# W010A.net
KiCad netlist of a schematic drawn in EAGLE
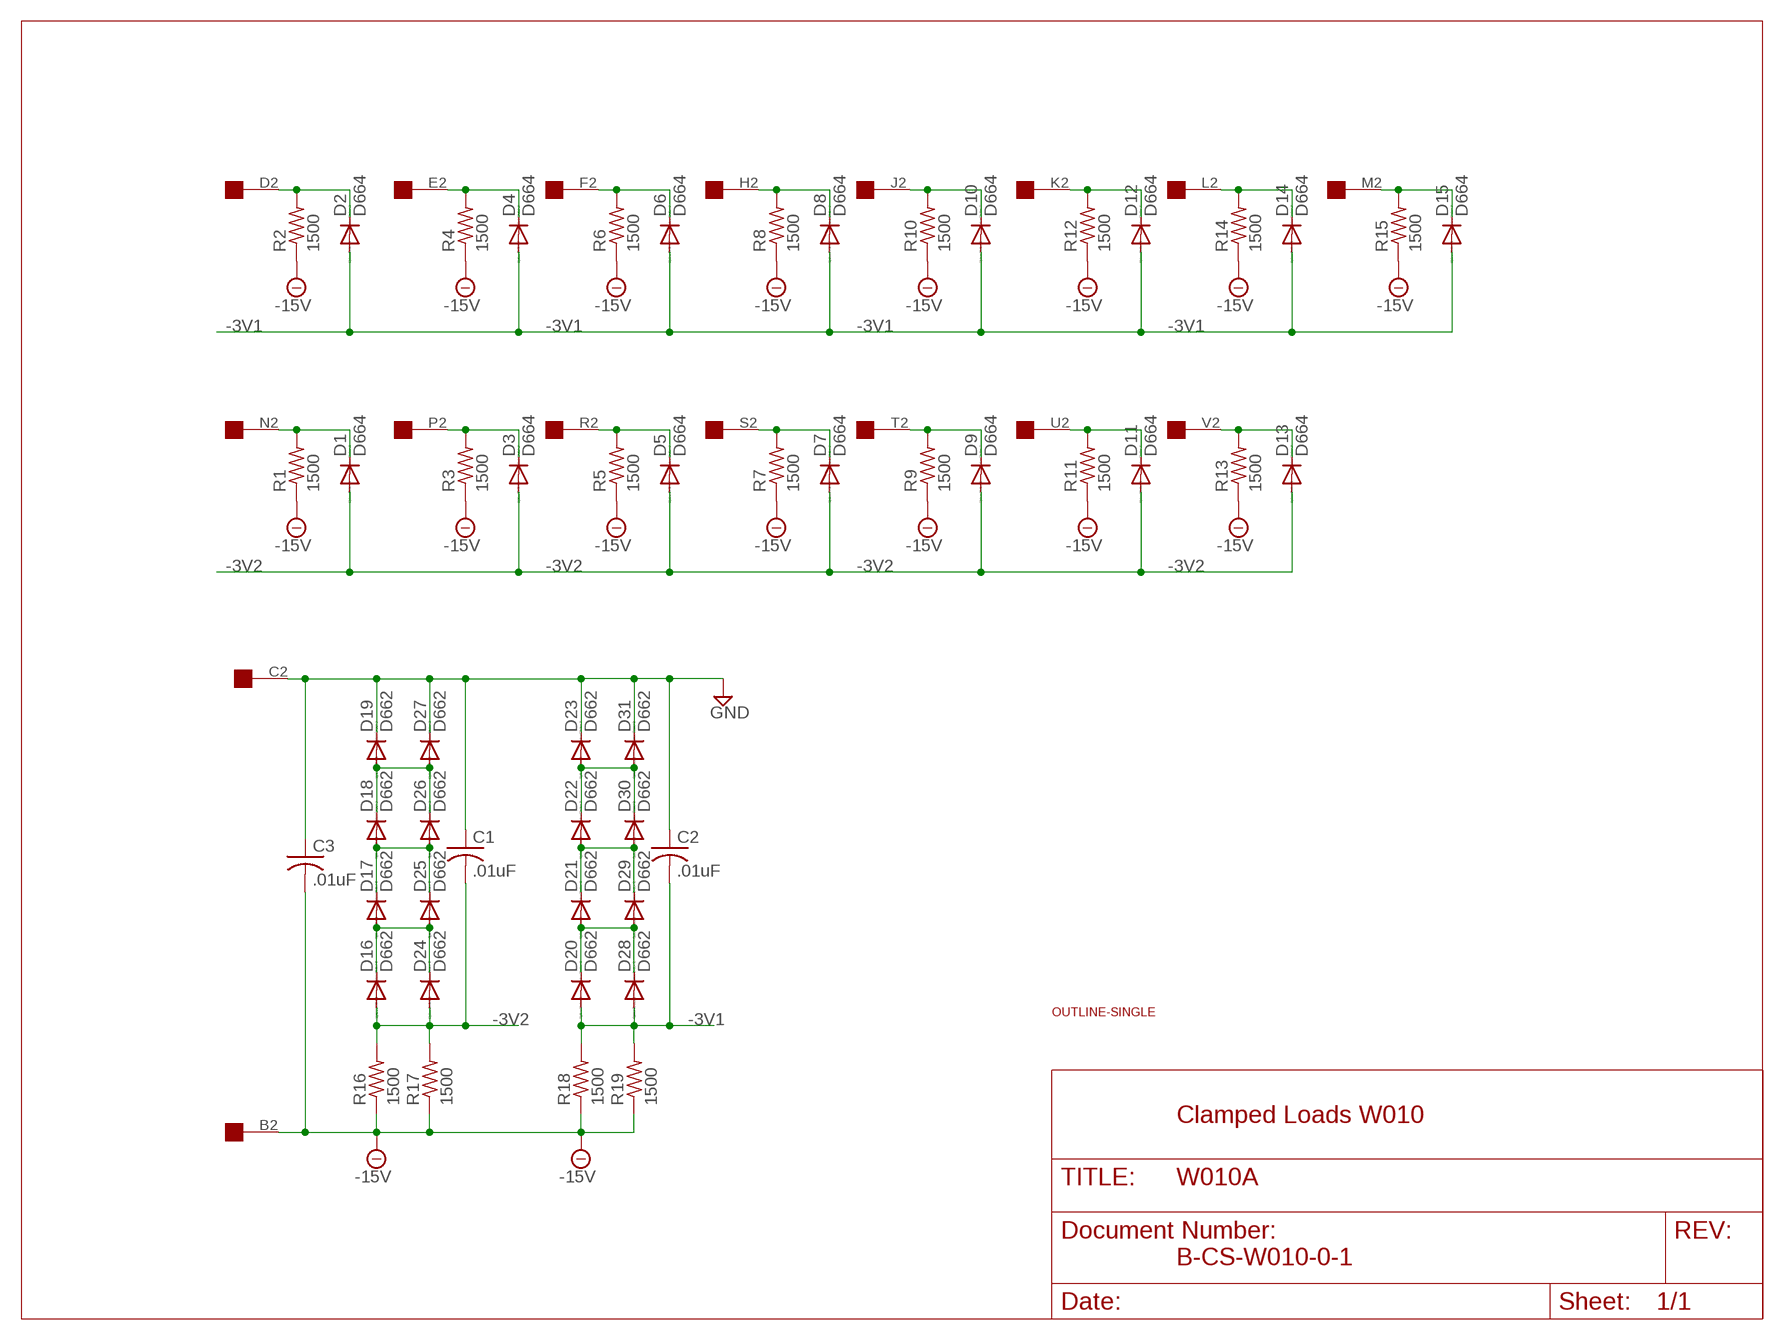
[diagram p0: schematic, sheet 1]

(export (version "E")
  (design (tool "Eeschema 10.0.6"))
  (components
    (comp (ref "C1")
      (value ".01uF")
      (footprint "eagle-import:C063-025X075")
      (libsource (lib "eagle-import") (part "C-US"))
    )
    (comp (ref "C2")
      (value ".01uF")
      (footprint "eagle-import:C063-025X075")
      (libsource (lib "eagle-import") (part "C-US"))
    )
    (comp (ref "C3")
      (value ".01uF")
      (footprint "eagle-import:C063-025X075")
      (libsource (lib "eagle-import") (part "C-US"))
    )
    (comp (ref "D1")
      (value "D664")
      (footprint "eagle-import:DO35-10")
      (libsource (lib "eagle-import") (part "DIODE-DO35-10"))
    )
    (comp (ref "D2")
      (value "D664")
      (footprint "eagle-import:DO35-10")
      (libsource (lib "eagle-import") (part "DIODE-DO35-10"))
    )
    (comp (ref "D3")
      (value "D664")
      (footprint "eagle-import:DO35-10")
      (libsource (lib "eagle-import") (part "DIODE-DO35-10"))
    )
    (comp (ref "D4")
      (value "D664")
      (footprint "eagle-import:DO35-10")
      (libsource (lib "eagle-import") (part "DIODE-DO35-10"))
    )
    (comp (ref "D5")
      (value "D664")
      (footprint "eagle-import:DO35-10")
      (libsource (lib "eagle-import") (part "DIODE-DO35-10"))
    )
    (comp (ref "D6")
      (value "D664")
      (footprint "eagle-import:DO35-10")
      (libsource (lib "eagle-import") (part "DIODE-DO35-10"))
    )
    (comp (ref "D7")
      (value "D664")
      (footprint "eagle-import:DO35-10")
      (libsource (lib "eagle-import") (part "DIODE-DO35-10"))
    )
    (comp (ref "D8")
      (value "D664")
      (footprint "eagle-import:DO35-10")
      (libsource (lib "eagle-import") (part "DIODE-DO35-10"))
    )
    (comp (ref "D9")
      (value "D664")
      (footprint "eagle-import:DO35-10")
      (libsource (lib "eagle-import") (part "DIODE-DO35-10"))
    )
    (comp (ref "D10")
      (value "D664")
      (footprint "eagle-import:DO35-10")
      (libsource (lib "eagle-import") (part "DIODE-DO35-10"))
    )
    (comp (ref "D11")
      (value "D664")
      (footprint "eagle-import:DO35-10")
      (libsource (lib "eagle-import") (part "DIODE-DO35-10"))
    )
    (comp (ref "D12")
      (value "D664")
      (footprint "eagle-import:DO35-10")
      (libsource (lib "eagle-import") (part "DIODE-DO35-10"))
    )
    (comp (ref "D13")
      (value "D664")
      (footprint "eagle-import:DO35-10")
      (libsource (lib "eagle-import") (part "DIODE-DO35-10"))
    )
    (comp (ref "D14")
      (value "D664")
      (footprint "eagle-import:DO35-10")
      (libsource (lib "eagle-import") (part "DIODE-DO35-10"))
    )
    (comp (ref "D15")
      (value "D664")
      (footprint "eagle-import:DO35-10")
      (libsource (lib "eagle-import") (part "DIODE-DO35-10"))
    )
    (comp (ref "D16")
      (value "D662")
      (footprint "eagle-import:DO35-10")
      (libsource (lib "eagle-import") (part "DIODE-DO35-10"))
    )
    (comp (ref "D17")
      (value "D662")
      (footprint "eagle-import:DO35-10")
      (libsource (lib "eagle-import") (part "DIODE-DO35-10"))
    )
    (comp (ref "D18")
      (value "D662")
      (footprint "eagle-import:DO35-10")
      (libsource (lib "eagle-import") (part "DIODE-DO35-10"))
    )
    (comp (ref "D19")
      (value "D662")
      (footprint "eagle-import:DO35-10")
      (libsource (lib "eagle-import") (part "DIODE-DO35-10"))
    )
    (comp (ref "D20")
      (value "D662")
      (footprint "eagle-import:DO35-10")
      (libsource (lib "eagle-import") (part "DIODE-DO35-10"))
    )
    (comp (ref "D21")
      (value "D662")
      (footprint "eagle-import:DO35-10")
      (libsource (lib "eagle-import") (part "DIODE-DO35-10"))
    )
    (comp (ref "D22")
      (value "D662")
      (footprint "eagle-import:DO35-10")
      (libsource (lib "eagle-import") (part "DIODE-DO35-10"))
    )
    (comp (ref "D23")
      (value "D662")
      (footprint "eagle-import:DO35-10")
      (libsource (lib "eagle-import") (part "DIODE-DO35-10"))
    )
    (comp (ref "D24")
      (value "D662")
      (footprint "eagle-import:DO35-10")
      (libsource (lib "eagle-import") (part "DIODE-DO35-10"))
    )
    (comp (ref "D25")
      (value "D662")
      (footprint "eagle-import:DO35-10")
      (libsource (lib "eagle-import") (part "DIODE-DO35-10"))
    )
    (comp (ref "D26")
      (value "D662")
      (footprint "eagle-import:DO35-10")
      (libsource (lib "eagle-import") (part "DIODE-DO35-10"))
    )
    (comp (ref "D27")
      (value "D662")
      (footprint "eagle-import:DO35-10")
      (libsource (lib "eagle-import") (part "DIODE-DO35-10"))
    )
    (comp (ref "D28")
      (value "D662")
      (footprint "eagle-import:DO35-10")
      (libsource (lib "eagle-import") (part "DIODE-DO35-10"))
    )
    (comp (ref "D29")
      (value "D662")
      (footprint "eagle-import:DO35-10")
      (libsource (lib "eagle-import") (part "DIODE-DO35-10"))
    )
    (comp (ref "D30")
      (value "D662")
      (footprint "eagle-import:DO35-10")
      (libsource (lib "eagle-import") (part "DIODE-DO35-10"))
    )
    (comp (ref "D31")
      (value "D662")
      (footprint "eagle-import:DO35-10")
      (libsource (lib "eagle-import") (part "DIODE-DO35-10"))
    )
    (comp (ref "R1")
      (value "1500")
      (footprint "eagle-import:0207_10")
      (libsource (lib "eagle-import") (part "R-US_0207/10"))
    )
    (comp (ref "R2")
      (value "1500")
      (footprint "eagle-import:0207_10")
      (libsource (lib "eagle-import") (part "R-US_0207/10"))
    )
    (comp (ref "R3")
      (value "1500")
      (footprint "eagle-import:0207_10")
      (libsource (lib "eagle-import") (part "R-US_0207/10"))
    )
    (comp (ref "R4")
      (value "1500")
      (footprint "eagle-import:0207_10")
      (libsource (lib "eagle-import") (part "R-US_0207/10"))
    )
    (comp (ref "R5")
      (value "1500")
      (footprint "eagle-import:0207_10")
      (libsource (lib "eagle-import") (part "R-US_0207/10"))
    )
    (comp (ref "R6")
      (value "1500")
      (footprint "eagle-import:0207_10")
      (libsource (lib "eagle-import") (part "R-US_0207/10"))
    )
    (comp (ref "R7")
      (value "1500")
      (footprint "eagle-import:0207_10")
      (libsource (lib "eagle-import") (part "R-US_0207/10"))
    )
    (comp (ref "R8")
      (value "1500")
      (footprint "eagle-import:0207_10")
      (libsource (lib "eagle-import") (part "R-US_0207/10"))
    )
    (comp (ref "R9")
      (value "1500")
      (footprint "eagle-import:0207_10")
      (libsource (lib "eagle-import") (part "R-US_0207/10"))
    )
    (comp (ref "R10")
      (value "1500")
      (footprint "eagle-import:0207_10")
      (libsource (lib "eagle-import") (part "R-US_0207/10"))
    )
    (comp (ref "R11")
      (value "1500")
      (footprint "eagle-import:0207_10")
      (libsource (lib "eagle-import") (part "R-US_0207/10"))
    )
    (comp (ref "R12")
      (value "1500")
      (footprint "eagle-import:0207_10")
      (libsource (lib "eagle-import") (part "R-US_0207/10"))
    )
    (comp (ref "R13")
      (value "1500")
      (footprint "eagle-import:0207_10")
      (libsource (lib "eagle-import") (part "R-US_0207/10"))
    )
    (comp (ref "R14")
      (value "1500")
      (footprint "eagle-import:0207_10")
      (libsource (lib "eagle-import") (part "R-US_0207/10"))
    )
    (comp (ref "R15")
      (value "1500")
      (footprint "eagle-import:0207_10")
      (libsource (lib "eagle-import") (part "R-US_0207/10"))
    )
    (comp (ref "R16")
      (value "1500")
      (footprint "eagle-import:0207_10")
      (libsource (lib "eagle-import") (part "R-US_0207/10"))
    )
    (comp (ref "R17")
      (value "1500")
      (footprint "eagle-import:0207_10")
      (libsource (lib "eagle-import") (part "R-US_0207/10"))
    )
    (comp (ref "R18")
      (value "1500")
      (footprint "eagle-import:0207_10")
      (libsource (lib "eagle-import") (part "R-US_0207/10"))
    )
    (comp (ref "R19")
      (value "1500")
      (footprint "eagle-import:0207_10")
      (libsource (lib "eagle-import") (part "R-US_0207/10"))
    )
    (comp (ref "U$1")
      (value "EDGE-1")
      (footprint "eagle-import:EDGE-CON1")
      (libsource (lib "eagle-import") (part "EDGE-1"))
    )
    (comp (ref "U$2")
      (value "OUTLINE-SINGLE")
      (footprint "eagle-import:SINGLE")
      (libsource (lib "eagle-import") (part "OUTLINE-SINGLE"))
    )
  )
  (nets
    (net (code "1") (name "-15V") (class "Default")
      (node (ref "C3") (pin "2") (pinfunction "2_2") (pintype "passive"))
      (node (ref "R1") (pin "1") (pinfunction "1_1") (pintype "passive"))
      (node (ref "R10") (pin "1") (pinfunction "1_1") (pintype "passive"))
      (node (ref "R11") (pin "1") (pinfunction "1_1") (pintype "passive"))
      (node (ref "R12") (pin "1") (pinfunction "1_1") (pintype "passive"))
      (node (ref "R13") (pin "1") (pinfunction "1_1") (pintype "passive"))
      (node (ref "R14") (pin "1") (pinfunction "1_1") (pintype "passive"))
      (node (ref "R15") (pin "1") (pinfunction "1_1") (pintype "passive"))
      (node (ref "R16") (pin "1") (pinfunction "1_1") (pintype "passive"))
      (node (ref "R17") (pin "1") (pinfunction "1_1") (pintype "passive"))
      (node (ref "R18") (pin "1") (pinfunction "1_1") (pintype "passive"))
      (node (ref "R19") (pin "1") (pinfunction "1_1") (pintype "passive"))
      (node (ref "R2") (pin "1") (pinfunction "1_1") (pintype "passive"))
      (node (ref "R3") (pin "1") (pinfunction "1_1") (pintype "passive"))
      (node (ref "R4") (pin "1") (pinfunction "1_1") (pintype "passive"))
      (node (ref "R5") (pin "1") (pinfunction "1_1") (pintype "passive"))
      (node (ref "R6") (pin "1") (pinfunction "1_1") (pintype "passive"))
      (node (ref "R7") (pin "1") (pinfunction "1_1") (pintype "passive"))
      (node (ref "R8") (pin "1") (pinfunction "1_1") (pintype "passive"))
      (node (ref "R9") (pin "1") (pinfunction "1_1") (pintype "passive"))
      (node (ref "U$1") (pin "B2") (pinfunction "1_B2") (pintype "bidirectional"))
    )
    (net (code "2") (name "/-3V1") (class "Default")
      (node (ref "C2") (pin "2") (pinfunction "2_2") (pintype "passive"))
      (node (ref "D10") (pin "A") (pinfunction "A_A") (pintype "passive"))
      (node (ref "D12") (pin "A") (pinfunction "A_A") (pintype "passive"))
      (node (ref "D14") (pin "A") (pinfunction "A_A") (pintype "passive"))
      (node (ref "D15") (pin "A") (pinfunction "A_A") (pintype "passive"))
      (node (ref "D2") (pin "A") (pinfunction "A_A") (pintype "passive"))
      (node (ref "D20") (pin "A") (pinfunction "A_A") (pintype "passive"))
      (node (ref "D28") (pin "A") (pinfunction "A_A") (pintype "passive"))
      (node (ref "D4") (pin "A") (pinfunction "A_A") (pintype "passive"))
      (node (ref "D6") (pin "A") (pinfunction "A_A") (pintype "passive"))
      (node (ref "D8") (pin "A") (pinfunction "A_A") (pintype "passive"))
      (node (ref "R18") (pin "2") (pinfunction "2_2") (pintype "passive"))
      (node (ref "R19") (pin "2") (pinfunction "2_2") (pintype "passive"))
    )
    (net (code "3") (name "/-3V2") (class "Default")
      (node (ref "C1") (pin "2") (pinfunction "2_2") (pintype "passive"))
      (node (ref "D1") (pin "A") (pinfunction "A_A") (pintype "passive"))
      (node (ref "D11") (pin "A") (pinfunction "A_A") (pintype "passive"))
      (node (ref "D13") (pin "A") (pinfunction "A_A") (pintype "passive"))
      (node (ref "D16") (pin "A") (pinfunction "A_A") (pintype "passive"))
      (node (ref "D24") (pin "A") (pinfunction "A_A") (pintype "passive"))
      (node (ref "D3") (pin "A") (pinfunction "A_A") (pintype "passive"))
      (node (ref "D5") (pin "A") (pinfunction "A_A") (pintype "passive"))
      (node (ref "D7") (pin "A") (pinfunction "A_A") (pintype "passive"))
      (node (ref "D9") (pin "A") (pinfunction "A_A") (pintype "passive"))
      (node (ref "R16") (pin "2") (pinfunction "2_2") (pintype "passive"))
      (node (ref "R17") (pin "2") (pinfunction "2_2") (pintype "passive"))
    )
    (net (code "4") (name "GND") (class "Default")
      (node (ref "C1") (pin "1") (pinfunction "1_1") (pintype "passive"))
      (node (ref "C2") (pin "1") (pinfunction "1_1") (pintype "passive"))
      (node (ref "C3") (pin "1") (pinfunction "1_1") (pintype "passive"))
      (node (ref "D19") (pin "C") (pinfunction "C_C") (pintype "passive"))
      (node (ref "D23") (pin "C") (pinfunction "C_C") (pintype "passive"))
      (node (ref "D27") (pin "C") (pinfunction "C_C") (pintype "passive"))
      (node (ref "D31") (pin "C") (pinfunction "C_C") (pintype "passive"))
      (node (ref "U$1") (pin "C2") (pinfunction "1_C2") (pintype "bidirectional"))
    )
    (net (code "5") (name "Net-(D16-PadC)") (class "Default")
      (node (ref "D16") (pin "C") (pinfunction "C_C") (pintype "passive"))
      (node (ref "D17") (pin "A") (pinfunction "A_A") (pintype "passive"))
      (node (ref "D24") (pin "C") (pinfunction "C_C") (pintype "passive"))
      (node (ref "D25") (pin "A") (pinfunction "A_A") (pintype "passive"))
    )
    (net (code "6") (name "Net-(D17-PadC)") (class "Default")
      (node (ref "D17") (pin "C") (pinfunction "C_C") (pintype "passive"))
      (node (ref "D18") (pin "A") (pinfunction "A_A") (pintype "passive"))
      (node (ref "D25") (pin "C") (pinfunction "C_C") (pintype "passive"))
      (node (ref "D26") (pin "A") (pinfunction "A_A") (pintype "passive"))
    )
    (net (code "7") (name "Net-(D18-PadC)") (class "Default")
      (node (ref "D18") (pin "C") (pinfunction "C_C") (pintype "passive"))
      (node (ref "D19") (pin "A") (pinfunction "A_A") (pintype "passive"))
      (node (ref "D26") (pin "C") (pinfunction "C_C") (pintype "passive"))
      (node (ref "D27") (pin "A") (pinfunction "A_A") (pintype "passive"))
    )
    (net (code "8") (name "Net-(D20-PadC)") (class "Default")
      (node (ref "D20") (pin "C") (pinfunction "C_C") (pintype "passive"))
      (node (ref "D21") (pin "A") (pinfunction "A_A") (pintype "passive"))
      (node (ref "D28") (pin "C") (pinfunction "C_C") (pintype "passive"))
      (node (ref "D29") (pin "A") (pinfunction "A_A") (pintype "passive"))
    )
    (net (code "9") (name "Net-(D21-PadC)") (class "Default")
      (node (ref "D21") (pin "C") (pinfunction "C_C") (pintype "passive"))
      (node (ref "D22") (pin "A") (pinfunction "A_A") (pintype "passive"))
      (node (ref "D29") (pin "C") (pinfunction "C_C") (pintype "passive"))
      (node (ref "D30") (pin "A") (pinfunction "A_A") (pintype "passive"))
    )
    (net (code "10") (name "Net-(D22-PadC)") (class "Default")
      (node (ref "D22") (pin "C") (pinfunction "C_C") (pintype "passive"))
      (node (ref "D23") (pin "A") (pinfunction "A_A") (pintype "passive"))
      (node (ref "D30") (pin "C") (pinfunction "C_C") (pintype "passive"))
      (node (ref "D31") (pin "A") (pinfunction "A_A") (pintype "passive"))
    )
    (net (code "11") (name "Net-(U$1D-1)") (class "Default")
      (node (ref "D2") (pin "C") (pinfunction "C_C") (pintype "passive"))
      (node (ref "R2") (pin "2") (pinfunction "2_2") (pintype "passive"))
      (node (ref "U$1") (pin "D2") (pinfunction "1_D2") (pintype "bidirectional"))
    )
    (net (code "12") (name "Net-(U$1E-1)") (class "Default")
      (node (ref "D4") (pin "C") (pinfunction "C_C") (pintype "passive"))
      (node (ref "R4") (pin "2") (pinfunction "2_2") (pintype "passive"))
      (node (ref "U$1") (pin "E2") (pinfunction "1_E2") (pintype "bidirectional"))
    )
    (net (code "13") (name "Net-(U$1F-1)") (class "Default")
      (node (ref "D6") (pin "C") (pinfunction "C_C") (pintype "passive"))
      (node (ref "R6") (pin "2") (pinfunction "2_2") (pintype "passive"))
      (node (ref "U$1") (pin "F2") (pinfunction "1_F2") (pintype "bidirectional"))
    )
    (net (code "14") (name "Net-(U$1G-1)") (class "Default")
      (node (ref "D8") (pin "C") (pinfunction "C_C") (pintype "passive"))
      (node (ref "R8") (pin "2") (pinfunction "2_2") (pintype "passive"))
      (node (ref "U$1") (pin "H2") (pinfunction "1_H2") (pintype "bidirectional"))
    )
    (net (code "15") (name "Net-(U$1H-1)") (class "Default")
      (node (ref "D10") (pin "C") (pinfunction "C_C") (pintype "passive"))
      (node (ref "R10") (pin "2") (pinfunction "2_2") (pintype "passive"))
      (node (ref "U$1") (pin "J2") (pinfunction "1_J2") (pintype "bidirectional"))
    )
    (net (code "16") (name "Net-(U$1I-1)") (class "Default")
      (node (ref "D12") (pin "C") (pinfunction "C_C") (pintype "passive"))
      (node (ref "R12") (pin "2") (pinfunction "2_2") (pintype "passive"))
      (node (ref "U$1") (pin "K2") (pinfunction "1_K2") (pintype "bidirectional"))
    )
    (net (code "17") (name "Net-(U$1J-1)") (class "Default")
      (node (ref "D14") (pin "C") (pinfunction "C_C") (pintype "passive"))
      (node (ref "R14") (pin "2") (pinfunction "2_2") (pintype "passive"))
      (node (ref "U$1") (pin "L2") (pinfunction "1_L2") (pintype "bidirectional"))
    )
    (net (code "18") (name "Net-(U$1K-1)") (class "Default")
      (node (ref "D15") (pin "C") (pinfunction "C_C") (pintype "passive"))
      (node (ref "R15") (pin "2") (pinfunction "2_2") (pintype "passive"))
      (node (ref "U$1") (pin "M2") (pinfunction "1_M2") (pintype "bidirectional"))
    )
    (net (code "19") (name "Net-(U$1L-1)") (class "Default")
      (node (ref "D1") (pin "C") (pinfunction "C_C") (pintype "passive"))
      (node (ref "R1") (pin "2") (pinfunction "2_2") (pintype "passive"))
      (node (ref "U$1") (pin "N2") (pinfunction "1_N2") (pintype "bidirectional"))
    )
    (net (code "20") (name "Net-(U$1M-1)") (class "Default")
      (node (ref "D3") (pin "C") (pinfunction "C_C") (pintype "passive"))
      (node (ref "R3") (pin "2") (pinfunction "2_2") (pintype "passive"))
      (node (ref "U$1") (pin "P2") (pinfunction "1_P2") (pintype "bidirectional"))
    )
    (net (code "21") (name "Net-(U$1N-1)") (class "Default")
      (node (ref "D5") (pin "C") (pinfunction "C_C") (pintype "passive"))
      (node (ref "R5") (pin "2") (pinfunction "2_2") (pintype "passive"))
      (node (ref "U$1") (pin "R2") (pinfunction "1_R2") (pintype "bidirectional"))
    )
    (net (code "22") (name "Net-(U$1O-1)") (class "Default")
      (node (ref "D7") (pin "C") (pinfunction "C_C") (pintype "passive"))
      (node (ref "R7") (pin "2") (pinfunction "2_2") (pintype "passive"))
      (node (ref "U$1") (pin "S2") (pinfunction "1_S2") (pintype "bidirectional"))
    )
    (net (code "23") (name "Net-(U$1P-1)") (class "Default")
      (node (ref "D9") (pin "C") (pinfunction "C_C") (pintype "passive"))
      (node (ref "R9") (pin "2") (pinfunction "2_2") (pintype "passive"))
      (node (ref "U$1") (pin "T2") (pinfunction "1_T2") (pintype "bidirectional"))
    )
    (net (code "24") (name "Net-(U$1Q-1)") (class "Default")
      (node (ref "D11") (pin "C") (pinfunction "C_C") (pintype "passive"))
      (node (ref "R11") (pin "2") (pinfunction "2_2") (pintype "passive"))
      (node (ref "U$1") (pin "U2") (pinfunction "1_U2") (pintype "bidirectional"))
    )
    (net (code "25") (name "Net-(U$1R-1)") (class "Default")
      (node (ref "D13") (pin "C") (pinfunction "C_C") (pintype "passive"))
      (node (ref "R13") (pin "2") (pinfunction "2_2") (pintype "passive"))
      (node (ref "U$1") (pin "V2") (pinfunction "1_V2") (pintype "bidirectional"))
    )
  )
)
